# TinyGController_V2.net
KiCad netlist of a schematic drawn in EAGLE
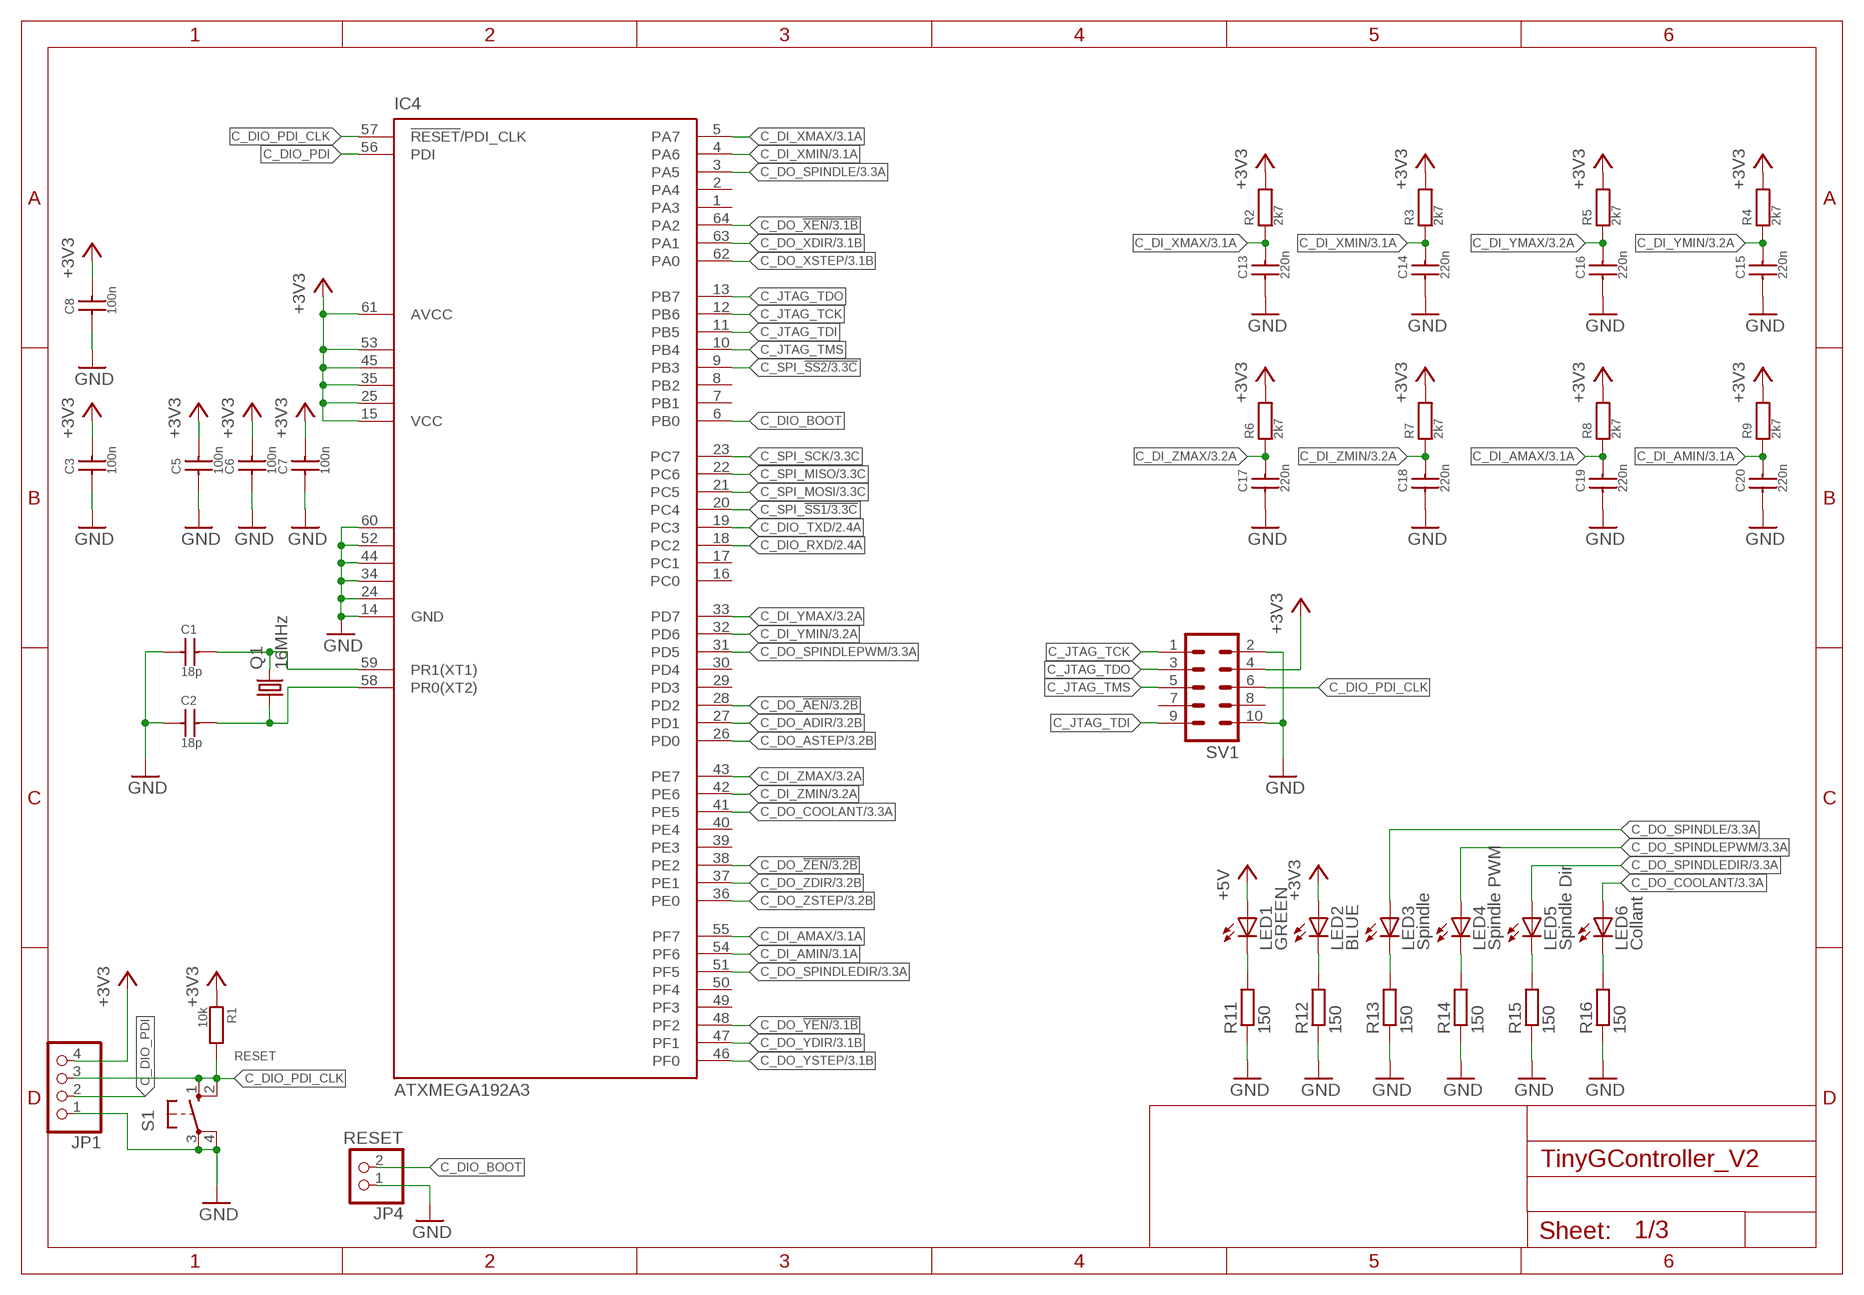
[diagram p0: schematic, sheet 1]
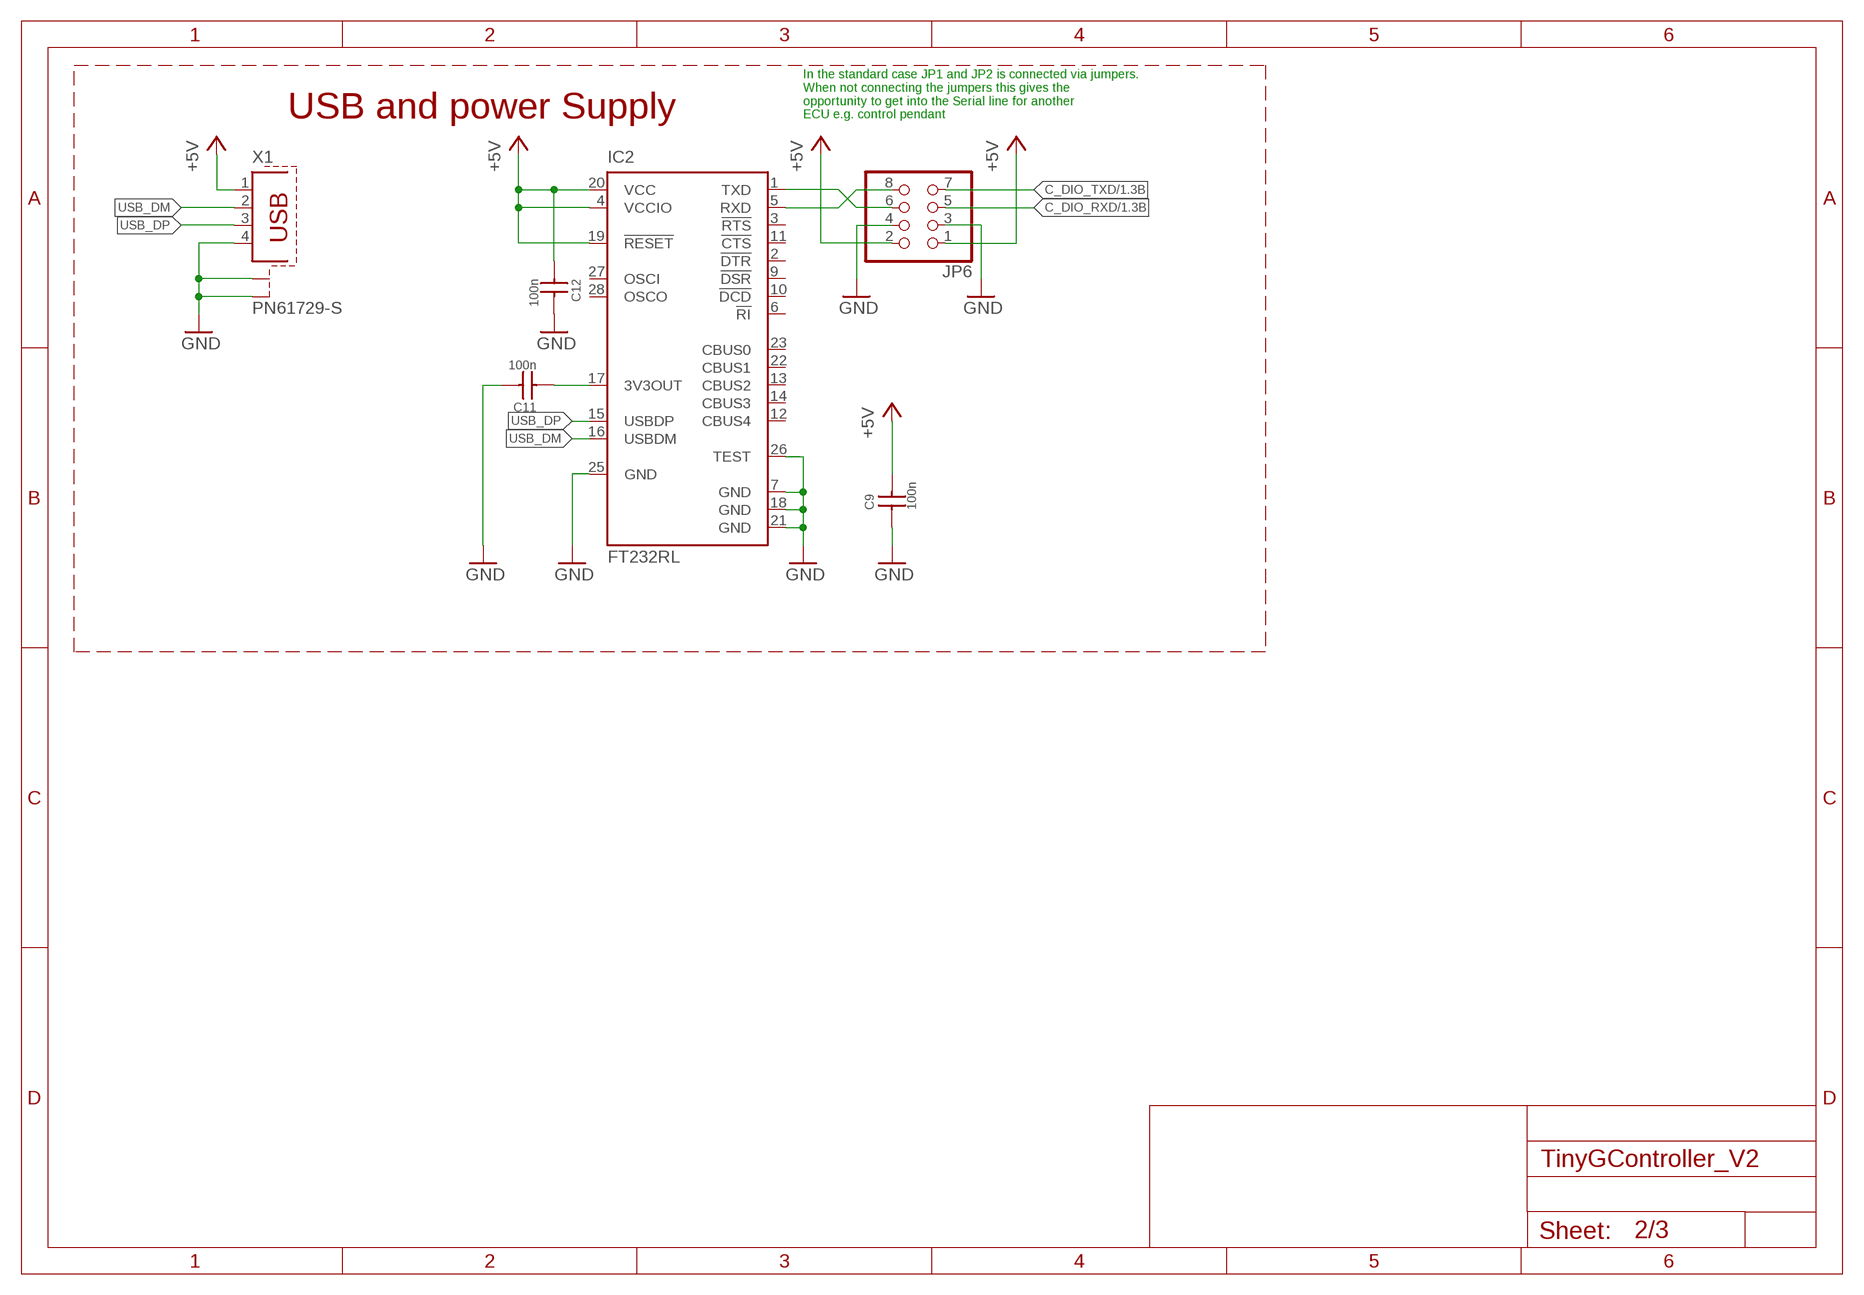
[diagram p1: schematic, sheet 2]
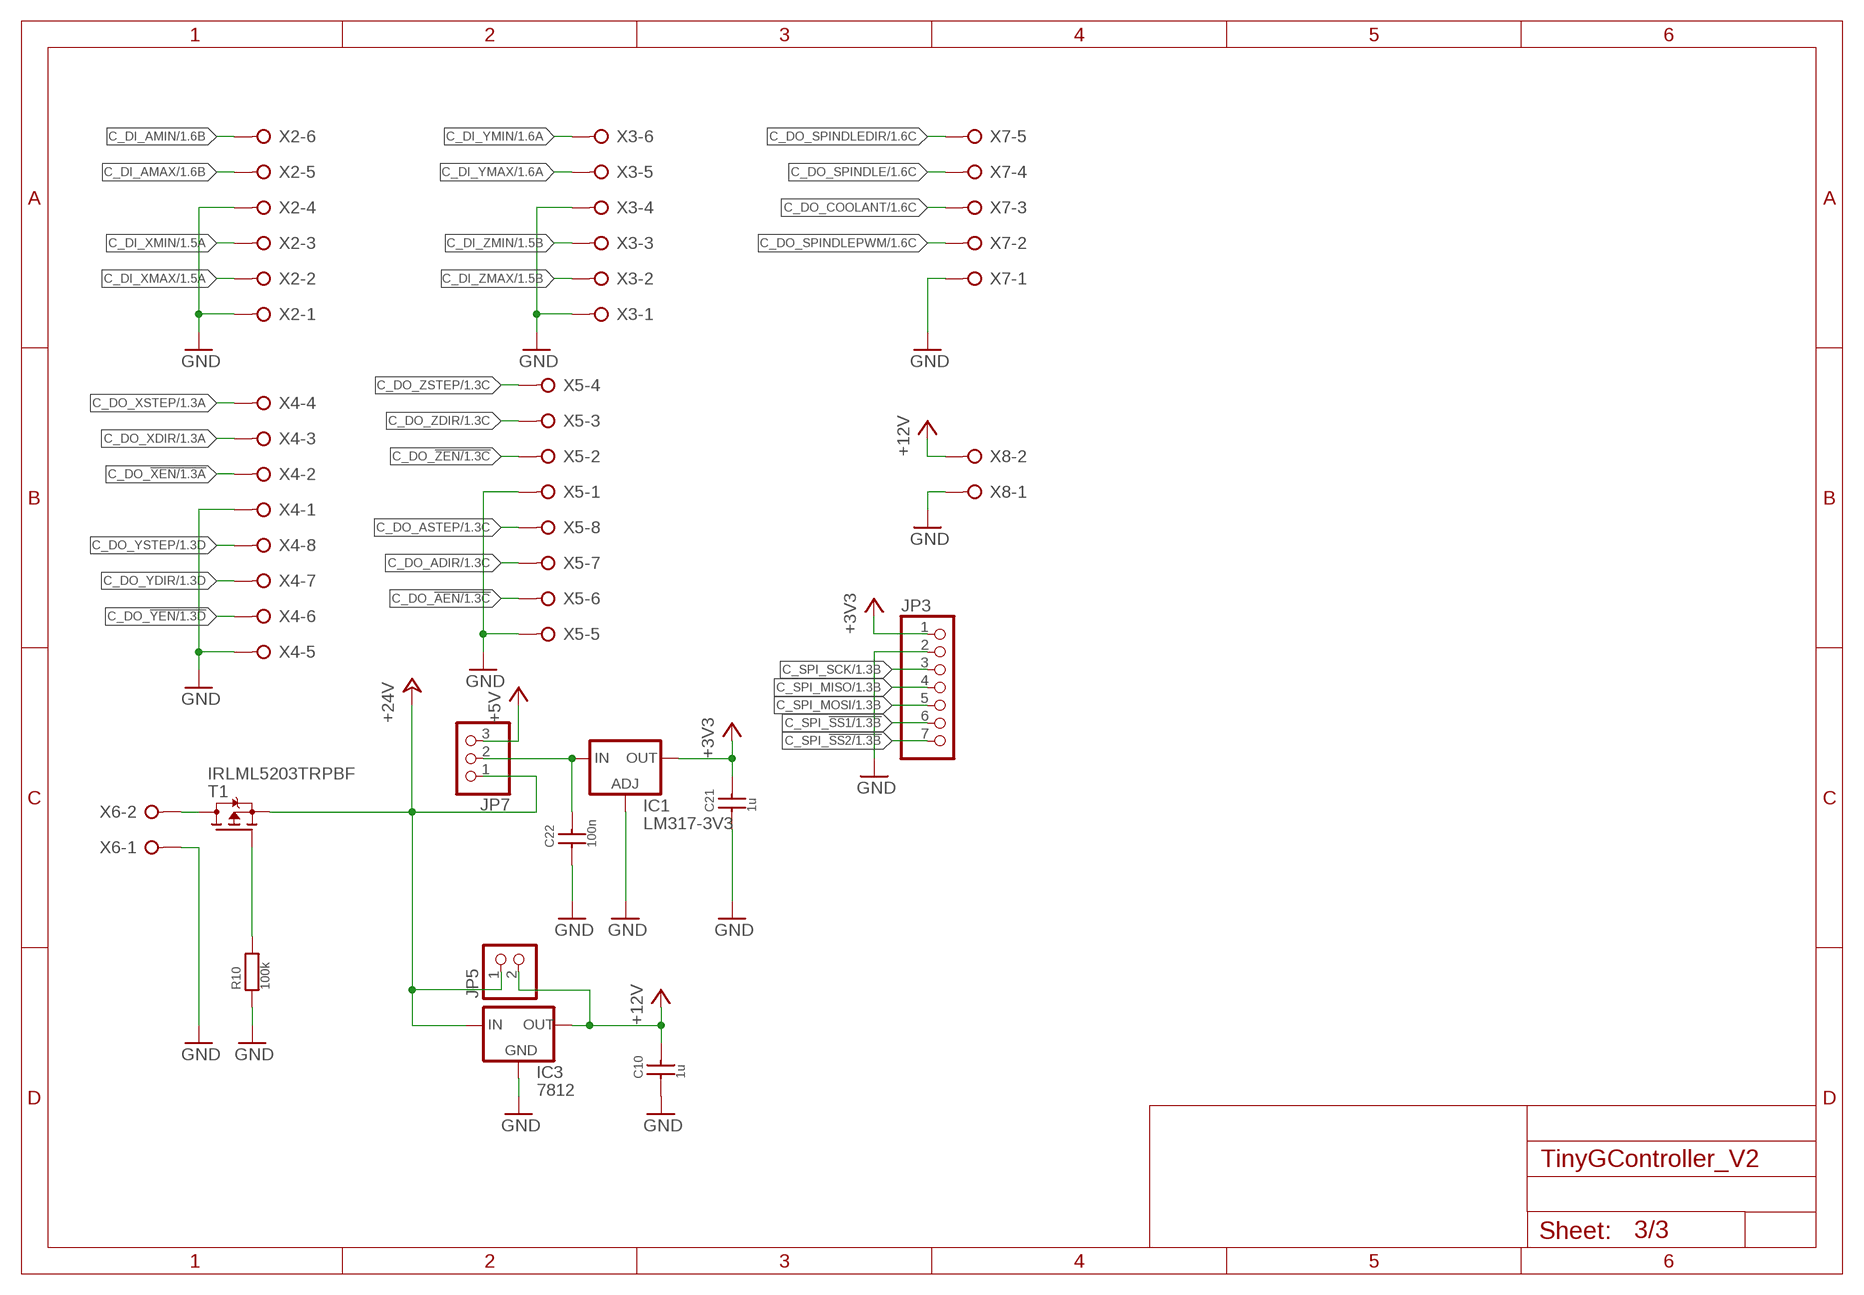
[diagram p2: schematic, sheet 3]

(export (version "E")
  (design (tool "Eeschema 10.0.6"))
  (components
    (comp (ref "C10")
      (value "1u")
      (footprint "eagle-import:C0805")
      (libsource (lib "eagle-import") (part "C_SMD0805"))
    )
    (comp (ref "C21")
      (value "1u")
      (footprint "eagle-import:C0805")
      (libsource (lib "eagle-import") (part "C_SMD0805"))
    )
    (comp (ref "C22")
      (value "100n")
      (footprint "eagle-import:C0805")
      (libsource (lib "eagle-import") (part "C_SMD0805"))
    )
    (comp (ref "IC1")
      (value "LM317-3V3")
      (footprint "eagle-import:SOT223")
      (libsource (lib "eagle-import") (part "LM317?MBSTT3"))
    )
    (comp (ref "IC3")
      (value "7812")
      (footprint "eagle-import:78XXS")
      (libsource (lib "eagle-import") (part "78XXS"))
    )
    (comp (ref "JP3")
      (value "PINHD-1X7")
      (footprint "eagle-import:1X07")
      (libsource (lib "eagle-import") (part "PINHD-1X7"))
    )
    (comp (ref "JP5")
      (value "PINHD-1X2")
      (footprint "eagle-import:1X02")
      (libsource (lib "eagle-import") (part "PINHD-1X2"))
    )
    (comp (ref "JP7")
      (value "PINHD-1X3")
      (footprint "eagle-import:1X03")
      (libsource (lib "eagle-import") (part "PINHD-1X3"))
    )
    (comp (ref "R10")
      (value "100k")
      (footprint "eagle-import:R0603")
      (libsource (lib "eagle-import") (part "R0603"))
    )
    (comp (ref "T1")
      (value "IRLML5203TRPBF")
      (footprint "eagle-import:SOT23")
      (libsource (lib "eagle-import") (part "IRLML5203TRPBF"))
    )
    (comp (ref "X2")
      (value "W237-06P")
      (footprint "eagle-import:W237-6P")
      (libsource (lib "eagle-import") (part "W237-06P"))
    )
    (comp (ref "X3")
      (value "W237-06P")
      (footprint "eagle-import:W237-6P")
      (libsource (lib "eagle-import") (part "W237-06P"))
    )
    (comp (ref "X4")
      (value "W237-08P")
      (footprint "eagle-import:W237-8P")
      (libsource (lib "eagle-import") (part "W237-08P"))
    )
    (comp (ref "X5")
      (value "W237-08P")
      (footprint "eagle-import:W237-8P")
      (libsource (lib "eagle-import") (part "W237-08P"))
    )
    (comp (ref "X6")
      (value "W237-02P")
      (footprint "eagle-import:W237-132")
      (libsource (lib "eagle-import") (part "W237-02P"))
    )
    (comp (ref "X7")
      (value "W237-05P")
      (footprint "eagle-import:W237-5P")
      (libsource (lib "eagle-import") (part "W237-05P"))
    )
    (comp (ref "X8")
      (value "W237-02P")
      (footprint "eagle-import:W237-132")
      (libsource (lib "eagle-import") (part "W237-02P"))
    )
    (comp (ref "C9")
      (value "100n")
      (footprint "eagle-import:C0603")
      (libsource (lib "eagle-import") (part "C_SMD0603"))
    )
    (comp (ref "C11")
      (value "100n")
      (footprint "eagle-import:C0603")
      (libsource (lib "eagle-import") (part "C_SMD0603"))
    )
    (comp (ref "C12")
      (value "100n")
      (footprint "eagle-import:C0603")
      (libsource (lib "eagle-import") (part "C_SMD0603"))
    )
    (comp (ref "IC2")
      (value "FT232RL")
      (footprint "eagle-import:SSOP28")
      (libsource (lib "eagle-import") (part "FT232RL"))
    )
    (comp (ref "JP6")
      (value "PINHD-2X4")
      (footprint "eagle-import:2X04")
      (libsource (lib "eagle-import") (part "PINHD-2X4"))
    )
    (comp (ref "X1")
      (value "PN61729-S")
      (footprint "eagle-import:PN61729-S")
      (libsource (lib "eagle-import") (part "PN61729-S"))
    )
    (comp (ref "C1")
      (value "18p")
      (footprint "eagle-import:C0603")
      (libsource (lib "eagle-import") (part "C_SMD0603"))
    )
    (comp (ref "C2")
      (value "18p")
      (footprint "eagle-import:C0603")
      (libsource (lib "eagle-import") (part "C_SMD0603"))
    )
    (comp (ref "C3")
      (value "100n")
      (footprint "eagle-import:C0603")
      (libsource (lib "eagle-import") (part "C_SMD0603"))
    )
    (comp (ref "C5")
      (value "100n")
      (footprint "eagle-import:C0603")
      (libsource (lib "eagle-import") (part "C_SMD0603"))
    )
    (comp (ref "C6")
      (value "100n")
      (footprint "eagle-import:C0603")
      (libsource (lib "eagle-import") (part "C_SMD0603"))
    )
    (comp (ref "C7")
      (value "100n")
      (footprint "eagle-import:C0603")
      (libsource (lib "eagle-import") (part "C_SMD0603"))
    )
    (comp (ref "C8")
      (value "100n")
      (footprint "eagle-import:C0603")
      (libsource (lib "eagle-import") (part "C_SMD0603"))
    )
    (comp (ref "C13")
      (value "220n")
      (footprint "eagle-import:C0805")
      (libsource (lib "eagle-import") (part "C_SMD0805"))
    )
    (comp (ref "C14")
      (value "220n")
      (footprint "eagle-import:C0805")
      (libsource (lib "eagle-import") (part "C_SMD0805"))
    )
    (comp (ref "C15")
      (value "220n")
      (footprint "eagle-import:C0805")
      (libsource (lib "eagle-import") (part "C_SMD0805"))
    )
    (comp (ref "C16")
      (value "220n")
      (footprint "eagle-import:C0805")
      (libsource (lib "eagle-import") (part "C_SMD0805"))
    )
    (comp (ref "C17")
      (value "220n")
      (footprint "eagle-import:C0805")
      (libsource (lib "eagle-import") (part "C_SMD0805"))
    )
    (comp (ref "C18")
      (value "220n")
      (footprint "eagle-import:C0805")
      (libsource (lib "eagle-import") (part "C_SMD0805"))
    )
    (comp (ref "C19")
      (value "220n")
      (footprint "eagle-import:C0805")
      (libsource (lib "eagle-import") (part "C_SMD0805"))
    )
    (comp (ref "C20")
      (value "220n")
      (footprint "eagle-import:C0805")
      (libsource (lib "eagle-import") (part "C_SMD0805"))
    )
    (comp (ref "IC4")
      (value "ATXMEGA192A3")
      (footprint "eagle-import:TQFP64-0.8MM")
      (libsource (lib "eagle-import") (part "ATXMEGA192A3"))
    )
    (comp (ref "JP1")
      (value "PINHD-1X4")
      (footprint "eagle-import:1X04")
      (libsource (lib "eagle-import") (part "PINHD-1X4"))
    )
    (comp (ref "JP4")
      (value "RESET")
      (footprint "eagle-import:1X02")
      (libsource (lib "eagle-import") (part "PINHD-1X2"))
    )
    (comp (ref "LED1")
      (value "GREEN")
      (footprint "eagle-import:CHIPLED_0805")
      (libsource (lib "eagle-import") (part "LEDCHIPLED_0805"))
    )
    (comp (ref "LED2")
      (value "BLUE")
      (footprint "eagle-import:CHIPLED_0805")
      (libsource (lib "eagle-import") (part "LEDCHIPLED_0805"))
    )
    (comp (ref "LED3")
      (value "Spindle")
      (footprint "eagle-import:CHIPLED_0805")
      (libsource (lib "eagle-import") (part "LEDCHIPLED_0805"))
    )
    (comp (ref "LED4")
      (value "Spindle PWM")
      (footprint "eagle-import:CHIPLED_0805")
      (libsource (lib "eagle-import") (part "LEDCHIPLED_0805"))
    )
    (comp (ref "LED5")
      (value "Spindle Dir")
      (footprint "eagle-import:CHIPLED_0805")
      (libsource (lib "eagle-import") (part "LEDCHIPLED_0805"))
    )
    (comp (ref "LED6")
      (value "Collant")
      (footprint "eagle-import:CHIPLED_0805")
      (libsource (lib "eagle-import") (part "LEDCHIPLED_0805"))
    )
    (comp (ref "Q1")
      (value "16MHz")
      (footprint "eagle-import:HC49_USSM")
      (libsource (lib "eagle-import") (part "ATS073ASM-1"))
    )
    (comp (ref "R1")
      (value "10k")
      (footprint "eagle-import:R0603")
      (libsource (lib "eagle-import") (part "R0603"))
    )
    (comp (ref "R2")
      (value "2k7")
      (footprint "eagle-import:R0603")
      (libsource (lib "eagle-import") (part "R0603"))
    )
    (comp (ref "R3")
      (value "2k7")
      (footprint "eagle-import:R0603")
      (libsource (lib "eagle-import") (part "R0603"))
    )
    (comp (ref "R4")
      (value "2k7")
      (footprint "eagle-import:R0603")
      (libsource (lib "eagle-import") (part "R0603"))
    )
    (comp (ref "R5")
      (value "2k7")
      (footprint "eagle-import:R0603")
      (libsource (lib "eagle-import") (part "R0603"))
    )
    (comp (ref "R6")
      (value "2k7")
      (footprint "eagle-import:R0603")
      (libsource (lib "eagle-import") (part "R0603"))
    )
    (comp (ref "R7")
      (value "2k7")
      (footprint "eagle-import:R0603")
      (libsource (lib "eagle-import") (part "R0603"))
    )
    (comp (ref "R8")
      (value "2k7")
      (footprint "eagle-import:R0603")
      (libsource (lib "eagle-import") (part "R0603"))
    )
    (comp (ref "R9")
      (value "2k7")
      (footprint "eagle-import:R0603")
      (libsource (lib "eagle-import") (part "R0603"))
    )
    (comp (ref "R11")
      (value "150")
      (footprint "eagle-import:R0603")
      (libsource (lib "eagle-import") (part "R-EU_R0603"))
    )
    (comp (ref "R12")
      (value "150")
      (footprint "eagle-import:R0603")
      (libsource (lib "eagle-import") (part "R-EU_R0603"))
    )
    (comp (ref "R13")
      (value "150")
      (footprint "eagle-import:R0603")
      (libsource (lib "eagle-import") (part "R-EU_R0603"))
    )
    (comp (ref "R14")
      (value "150")
      (footprint "eagle-import:R0603")
      (libsource (lib "eagle-import") (part "R-EU_R0603"))
    )
    (comp (ref "R15")
      (value "150")
      (footprint "eagle-import:R0603")
      (libsource (lib "eagle-import") (part "R-EU_R0603"))
    )
    (comp (ref "R16")
      (value "150")
      (footprint "eagle-import:R0603")
      (libsource (lib "eagle-import") (part "R-EU_R0603"))
    )
    (comp (ref "S1")
      (value "10-XX")
      (footprint "eagle-import:B3F-10XX")
      (fields (field (name "MPN") "B3F-1000"))
      (libsource (lib "eagle-import") (part "10-XX"))
    )
    (comp (ref "SV1")
      (value "ML10")
      (footprint "eagle-import:ML10")
      (libsource (lib "eagle-import") (part "ML10"))
    )
  )
  (nets
    (net (code "1") (name "+3V3") (class "Default")
      (node (ref "C21") (pin "2") (pinfunction "P$2_2") (pintype "passive"))
      (node (ref "C3") (pin "2") (pinfunction "P$2_2") (pintype "passive"))
      (node (ref "C5") (pin "2") (pinfunction "P$2_2") (pintype "passive"))
      (node (ref "C6") (pin "2") (pinfunction "P$2_2") (pintype "passive"))
      (node (ref "C7") (pin "2") (pinfunction "P$2_2") (pintype "passive"))
      (node (ref "C8") (pin "2") (pinfunction "P$2_2") (pintype "passive"))
      (node (ref "IC1") (pin "4") (pinfunction "OUT_4") (pintype "passive"))
      (node (ref "IC4") (pin "15") (pinfunction "VCC_15") (pintype "power_in"))
      (node (ref "IC4") (pin "25") (pinfunction "VCC1_25") (pintype "power_in"))
      (node (ref "IC4") (pin "35") (pinfunction "VCC2_35") (pintype "power_in"))
      (node (ref "IC4") (pin "45") (pinfunction "VCC3_45") (pintype "power_in"))
      (node (ref "IC4") (pin "53") (pinfunction "VCC4_53") (pintype "power_in"))
      (node (ref "IC4") (pin "61") (pinfunction "AVCC_61") (pintype "power_in"))
      (node (ref "JP1") (pin "4") (pinfunction "4_4") (pintype "passive"))
      (node (ref "JP3") (pin "1") (pinfunction "1_1") (pintype "passive"))
      (node (ref "LED2") (pin "A") (pinfunction "A_A") (pintype "passive"))
      (node (ref "R1") (pin "1") (pinfunction "P$1_1") (pintype "passive"))
      (node (ref "R2") (pin "2") (pinfunction "P$2_2") (pintype "passive"))
      (node (ref "R3") (pin "2") (pinfunction "P$2_2") (pintype "passive"))
      (node (ref "R4") (pin "2") (pinfunction "P$2_2") (pintype "passive"))
      (node (ref "R5") (pin "2") (pinfunction "P$2_2") (pintype "passive"))
      (node (ref "R6") (pin "2") (pinfunction "P$2_2") (pintype "passive"))
      (node (ref "R7") (pin "2") (pinfunction "P$2_2") (pintype "passive"))
      (node (ref "R8") (pin "2") (pinfunction "P$2_2") (pintype "passive"))
      (node (ref "R9") (pin "2") (pinfunction "P$2_2") (pintype "passive"))
      (node (ref "SV1") (pin "4") (pinfunction "4_4") (pintype "passive"))
    )
    (net (code "2") (name "+5V") (class "Default")
      (node (ref "C12") (pin "1") (pinfunction "P$1_1") (pintype "passive"))
      (node (ref "C9") (pin "2") (pinfunction "P$2_2") (pintype "passive"))
      (node (ref "IC2") (pin "19") (pinfunction "~{RESET}_19") (pintype "input"))
      (node (ref "IC2") (pin "20") (pinfunction "VCC_20") (pintype "power_in"))
      (node (ref "IC2") (pin "4") (pinfunction "VCCIO_4") (pintype "power_in"))
      (node (ref "JP6") (pin "1") (pinfunction "1_1") (pintype "passive"))
      (node (ref "JP6") (pin "2") (pinfunction "2_2") (pintype "passive"))
      (node (ref "JP7") (pin "3") (pinfunction "3_3") (pintype "passive"))
      (node (ref "LED1") (pin "A") (pinfunction "A_A") (pintype "passive"))
      (node (ref "X1") (pin "1") (pinfunction "1_1") (pintype "passive"))
    )
    (net (code "3") (name "+12V") (class "Default")
      (node (ref "C10") (pin "2") (pinfunction "P$2_2") (pintype "passive"))
      (node (ref "IC3") (pin "OUT") (pinfunction "OUT_OUT") (pintype "passive"))
      (node (ref "JP5") (pin "2") (pinfunction "2_2") (pintype "passive"))
      (node (ref "X8") (pin "2") (pinfunction "KL_2") (pintype "passive"))
    )
    (net (code "4") (name "+24V") (class "Default")
      (node (ref "IC3") (pin "IN") (pinfunction "IN_IN") (pintype "input"))
      (node (ref "JP5") (pin "1") (pinfunction "1_1") (pintype "passive"))
      (node (ref "JP7") (pin "1") (pinfunction "1_1") (pintype "passive"))
      (node (ref "T1") (pin "2") (pinfunction "S_2") (pintype "passive"))
    )
    (net (code "5") (name "C_DIO_BOOT") (class "Default")
      (node (ref "IC4") (pin "6") (pinfunction "PB0_6") (pintype "bidirectional"))
      (node (ref "JP4") (pin "2") (pinfunction "2_2") (pintype "passive"))
    )
    (net (code "6") (name "C_DIO_PDI") (class "Default")
      (node (ref "IC4") (pin "56") (pinfunction "PDI_56") (pintype "input"))
      (node (ref "JP1") (pin "2") (pinfunction "2_2") (pintype "passive"))
    )
    (net (code "7") (name "C_DIO_PDI_CLK") (class "Default")
      (node (ref "IC4") (pin "57") (pinfunction "~{RESET}/PDI_CLK_57") (pintype "input"))
      (node (ref "JP1") (pin "3") (pinfunction "3_3") (pintype "passive"))
      (node (ref "R1") (pin "2") (pinfunction "P$2_2") (pintype "passive"))
      (node (ref "S1") (pin "1") (pinfunction "S_1") (pintype "passive"))
      (node (ref "S1") (pin "2") (pinfunction "S1_2") (pintype "passive"))
      (node (ref "SV1") (pin "6") (pinfunction "6_6") (pintype "passive"))
    )
    (net (code "8") (name "C_DIO_RXD") (class "Default")
      (node (ref "IC4") (pin "18") (pinfunction "PC2_18") (pintype "bidirectional"))
      (node (ref "JP6") (pin "5") (pinfunction "5_5") (pintype "passive"))
    )
    (net (code "9") (name "C_DIO_TXD") (class "Default")
      (node (ref "IC4") (pin "19") (pinfunction "PC3_19") (pintype "bidirectional"))
      (node (ref "JP6") (pin "7") (pinfunction "7_7") (pintype "passive"))
    )
    (net (code "10") (name "C_DI_AMAX") (class "Default")
      (node (ref "C19") (pin "2") (pinfunction "P$2_2") (pintype "passive"))
      (node (ref "IC4") (pin "55") (pinfunction "PF7_55") (pintype "bidirectional"))
      (node (ref "R8") (pin "1") (pinfunction "P$1_1") (pintype "passive"))
      (node (ref "X2") (pin "5") (pinfunction "KL_5") (pintype "passive"))
    )
    (net (code "11") (name "C_DI_AMIN") (class "Default")
      (node (ref "C20") (pin "2") (pinfunction "P$2_2") (pintype "passive"))
      (node (ref "IC4") (pin "54") (pinfunction "PF6_54") (pintype "bidirectional"))
      (node (ref "R9") (pin "1") (pinfunction "P$1_1") (pintype "passive"))
      (node (ref "X2") (pin "6") (pinfunction "KL_6") (pintype "passive"))
    )
    (net (code "12") (name "C_DI_XMAX") (class "Default")
      (node (ref "C13") (pin "2") (pinfunction "P$2_2") (pintype "passive"))
      (node (ref "IC4") (pin "5") (pinfunction "PA7_5") (pintype "bidirectional"))
      (node (ref "R2") (pin "1") (pinfunction "P$1_1") (pintype "passive"))
      (node (ref "X2") (pin "2") (pinfunction "KL_2") (pintype "passive"))
    )
    (net (code "13") (name "C_DI_XMIN") (class "Default")
      (node (ref "C14") (pin "2") (pinfunction "P$2_2") (pintype "passive"))
      (node (ref "IC4") (pin "4") (pinfunction "PA6_4") (pintype "bidirectional"))
      (node (ref "R3") (pin "1") (pinfunction "P$1_1") (pintype "passive"))
      (node (ref "X2") (pin "3") (pinfunction "KL_3") (pintype "passive"))
    )
    (net (code "14") (name "C_DI_YMAX") (class "Default")
      (node (ref "C16") (pin "2") (pinfunction "P$2_2") (pintype "passive"))
      (node (ref "IC4") (pin "33") (pinfunction "PD7_33") (pintype "bidirectional"))
      (node (ref "R5") (pin "1") (pinfunction "P$1_1") (pintype "passive"))
      (node (ref "X3") (pin "5") (pinfunction "KL_5") (pintype "passive"))
    )
    (net (code "15") (name "C_DI_YMIN") (class "Default")
      (node (ref "C15") (pin "2") (pinfunction "P$2_2") (pintype "passive"))
      (node (ref "IC4") (pin "32") (pinfunction "PD6_32") (pintype "bidirectional"))
      (node (ref "R4") (pin "1") (pinfunction "P$1_1") (pintype "passive"))
      (node (ref "X3") (pin "6") (pinfunction "KL_6") (pintype "passive"))
    )
    (net (code "16") (name "C_DI_ZMAX") (class "Default")
      (node (ref "C17") (pin "2") (pinfunction "P$2_2") (pintype "passive"))
      (node (ref "IC4") (pin "43") (pinfunction "PE7_43") (pintype "bidirectional"))
      (node (ref "R6") (pin "1") (pinfunction "P$1_1") (pintype "passive"))
      (node (ref "X3") (pin "2") (pinfunction "KL_2") (pintype "passive"))
    )
    (net (code "17") (name "C_DI_ZMIN") (class "Default")
      (node (ref "C18") (pin "2") (pinfunction "P$2_2") (pintype "passive"))
      (node (ref "IC4") (pin "42") (pinfunction "PE6_42") (pintype "bidirectional"))
      (node (ref "R7") (pin "1") (pinfunction "P$1_1") (pintype "passive"))
      (node (ref "X3") (pin "3") (pinfunction "KL_3") (pintype "passive"))
    )
    (net (code "18") (name "C_DO_ADIR") (class "Default")
      (node (ref "IC4") (pin "27") (pinfunction "PD1_27") (pintype "bidirectional"))
      (node (ref "X5") (pin "7") (pinfunction "KL_7") (pintype "passive"))
    )
    (net (code "19") (name "C_DO_ASTEP") (class "Default")
      (node (ref "IC4") (pin "26") (pinfunction "PD0_26") (pintype "bidirectional"))
      (node (ref "X5") (pin "8") (pinfunction "KL_8") (pintype "passive"))
    )
    (net (code "20") (name "C_DO_COOLANT") (class "Default")
      (node (ref "IC4") (pin "41") (pinfunction "PE5_41") (pintype "bidirectional"))
      (node (ref "LED6") (pin "A") (pinfunction "A_A") (pintype "passive"))
      (node (ref "X7") (pin "3") (pinfunction "KL_3") (pintype "passive"))
    )
    (net (code "21") (name "C_DO_SPINDLE") (class "Default")
      (node (ref "IC4") (pin "3") (pinfunction "PA5_3") (pintype "bidirectional"))
      (node (ref "LED3") (pin "A") (pinfunction "A_A") (pintype "passive"))
      (node (ref "X7") (pin "4") (pinfunction "KL_4") (pintype "passive"))
    )
    (net (code "22") (name "C_DO_SPINDLEDIR") (class "Default")
      (node (ref "IC4") (pin "51") (pinfunction "PF5_51") (pintype "bidirectional"))
      (node (ref "LED5") (pin "A") (pinfunction "A_A") (pintype "passive"))
      (node (ref "X7") (pin "5") (pinfunction "KL_5") (pintype "passive"))
    )
    (net (code "23") (name "C_DO_SPINDLEPWM") (class "Default")
      (node (ref "IC4") (pin "31") (pinfunction "PD5_31") (pintype "bidirectional"))
      (node (ref "LED4") (pin "A") (pinfunction "A_A") (pintype "passive"))
      (node (ref "X7") (pin "2") (pinfunction "KL_2") (pintype "passive"))
    )
    (net (code "24") (name "C_DO_XDIR") (class "Default")
      (node (ref "IC4") (pin "63") (pinfunction "PA1_63") (pintype "bidirectional"))
      (node (ref "X4") (pin "3") (pinfunction "KL_3") (pintype "passive"))
    )
    (net (code "25") (name "C_DO_XSTEP") (class "Default")
      (node (ref "IC4") (pin "62") (pinfunction "PA0_62") (pintype "bidirectional"))
      (node (ref "X4") (pin "4") (pinfunction "KL_4") (pintype "passive"))
    )
    (net (code "26") (name "C_DO_YDIR") (class "Default")
      (node (ref "IC4") (pin "47") (pinfunction "PF1_47") (pintype "bidirectional"))
      (node (ref "X4") (pin "7") (pinfunction "KL_7") (pintype "passive"))
    )
    (net (code "27") (name "C_DO_YSTEP") (class "Default")
      (node (ref "IC4") (pin "46") (pinfunction "PF0_46") (pintype "bidirectional"))
      (node (ref "X4") (pin "8") (pinfunction "KL_8") (pintype "passive"))
    )
    (net (code "28") (name "C_DO_ZDIR") (class "Default")
      (node (ref "IC4") (pin "37") (pinfunction "PE1_37") (pintype "bidirectional"))
      (node (ref "X5") (pin "3") (pinfunction "KL_3") (pintype "passive"))
    )
    (net (code "29") (name "C_DO_ZSTEP") (class "Default")
      (node (ref "IC4") (pin "36") (pinfunction "PE0_36") (pintype "bidirectional"))
      (node (ref "X5") (pin "4") (pinfunction "KL_4") (pintype "passive"))
    )
    (net (code "30") (name "C_DO_~{AEN}") (class "Default")
      (node (ref "IC4") (pin "28") (pinfunction "PD2_28") (pintype "bidirectional"))
      (node (ref "X5") (pin "6") (pinfunction "KL_6") (pintype "passive"))
    )
    (net (code "31") (name "C_DO_~{XEN}") (class "Default")
      (node (ref "IC4") (pin "64") (pinfunction "PA2_64") (pintype "bidirectional"))
      (node (ref "X4") (pin "2") (pinfunction "KL_2") (pintype "passive"))
    )
    (net (code "32") (name "C_DO_~{YEN}") (class "Default")
      (node (ref "IC4") (pin "48") (pinfunction "PF2_48") (pintype "bidirectional"))
      (node (ref "X4") (pin "6") (pinfunction "KL_6") (pintype "passive"))
    )
    (net (code "33") (name "C_DO_~{ZEN}") (class "Default")
      (node (ref "IC4") (pin "38") (pinfunction "PE2_38") (pintype "bidirectional"))
      (node (ref "X5") (pin "2") (pinfunction "KL_2") (pintype "passive"))
    )
    (net (code "34") (name "C_JTAG_TCK") (class "Default")
      (node (ref "IC4") (pin "12") (pinfunction "PB6_12") (pintype "bidirectional"))
      (node (ref "SV1") (pin "1") (pinfunction "1_1") (pintype "passive"))
    )
    (net (code "35") (name "C_JTAG_TDI") (class "Default")
      (node (ref "IC4") (pin "11") (pinfunction "PB5_11") (pintype "bidirectional"))
      (node (ref "SV1") (pin "9") (pinfunction "9_9") (pintype "passive"))
    )
    (net (code "36") (name "C_JTAG_TDO") (class "Default")
      (node (ref "IC4") (pin "13") (pinfunction "PB7_13") (pintype "bidirectional"))
      (node (ref "SV1") (pin "3") (pinfunction "3_3") (pintype "passive"))
    )
    (net (code "37") (name "C_JTAG_TMS") (class "Default")
      (node (ref "IC4") (pin "10") (pinfunction "PB4_10") (pintype "bidirectional"))
      (node (ref "SV1") (pin "5") (pinfunction "5_5") (pintype "passive"))
    )
    (net (code "38") (name "C_SPI_MISO") (class "Default")
      (node (ref "IC4") (pin "22") (pinfunction "PC6_22") (pintype "bidirectional"))
      (node (ref "JP3") (pin "4") (pinfunction "4_4") (pintype "passive"))
    )
    (net (code "39") (name "C_SPI_MOSI") (class "Default")
      (node (ref "IC4") (pin "21") (pinfunction "PC5_21") (pintype "bidirectional"))
      (node (ref "JP3") (pin "5") (pinfunction "5_5") (pintype "passive"))
    )
    (net (code "40") (name "C_SPI_SCK") (class "Default")
      (node (ref "IC4") (pin "23") (pinfunction "PC7_23") (pintype "bidirectional"))
      (node (ref "JP3") (pin "3") (pinfunction "3_3") (pintype "passive"))
    )
    (net (code "41") (name "C_SPI_~{SS1}") (class "Default")
      (node (ref "IC4") (pin "20") (pinfunction "PC4_20") (pintype "bidirectional"))
      (node (ref "JP3") (pin "6") (pinfunction "6_6") (pintype "passive"))
    )
    (net (code "42") (name "C_SPI_~{SS2}") (class "Default")
      (node (ref "IC4") (pin "9") (pinfunction "PB3_9") (pintype "bidirectional"))
      (node (ref "JP3") (pin "7") (pinfunction "7_7") (pintype "passive"))
    )
    (net (code "43") (name "GND") (class "Default")
      (node (ref "C1") (pin "1") (pinfunction "P$1_1") (pintype "passive"))
      (node (ref "C10") (pin "1") (pinfunction "P$1_1") (pintype "passive"))
      (node (ref "C11") (pin "2") (pinfunction "P$2_2") (pintype "passive"))
      (node (ref "C12") (pin "2") (pinfunction "P$2_2") (pintype "passive"))
      (node (ref "C13") (pin "1") (pinfunction "P$1_1") (pintype "passive"))
      (node (ref "C14") (pin "1") (pinfunction "P$1_1") (pintype "passive"))
      (node (ref "C15") (pin "1") (pinfunction "P$1_1") (pintype "passive"))
      (node (ref "C16") (pin "1") (pinfunction "P$1_1") (pintype "passive"))
      (node (ref "C17") (pin "1") (pinfunction "P$1_1") (pintype "passive"))
      (node (ref "C18") (pin "1") (pinfunction "P$1_1") (pintype "passive"))
      (node (ref "C19") (pin "1") (pinfunction "P$1_1") (pintype "passive"))
      (node (ref "C2") (pin "1") (pinfunction "P$1_1") (pintype "passive"))
      (node (ref "C20") (pin "1") (pinfunction "P$1_1") (pintype "passive"))
      (node (ref "C21") (pin "1") (pinfunction "P$1_1") (pintype "passive"))
      (node (ref "C22") (pin "1") (pinfunction "P$1_1") (pintype "passive"))
      (node (ref "C3") (pin "1") (pinfunction "P$1_1") (pintype "passive"))
      (node (ref "C5") (pin "1") (pinfunction "P$1_1") (pintype "passive"))
      (node (ref "C6") (pin "1") (pinfunction "P$1_1") (pintype "passive"))
      (node (ref "C7") (pin "1") (pinfunction "P$1_1") (pintype "passive"))
      (node (ref "C8") (pin "1") (pinfunction "P$1_1") (pintype "passive"))
      (node (ref "C9") (pin "1") (pinfunction "P$1_1") (pintype "passive"))
      (node (ref "IC1") (pin "1") (pinfunction "ADJ_1") (pintype "input"))
      (node (ref "IC2") (pin "18") (pinfunction "GND_18") (pintype "power_in"))
      (node (ref "IC2") (pin "21") (pinfunction "GND_21") (pintype "power_in"))
      (node (ref "IC2") (pin "25") (pinfunction "GND_25") (pintype "power_in"))
      (node (ref "IC2") (pin "26") (pinfunction "TEST_26") (pintype "input"))
      (node (ref "IC2") (pin "7") (pinfunction "GND_7") (pintype "power_in"))
      (node (ref "IC3") (pin "GND") (pinfunction "GND_GND") (pintype "input"))
      (node (ref "IC4") (pin "14") (pinfunction "GND_14") (pintype "power_in"))
      (node (ref "IC4") (pin "24") (pinfunction "GND1_24") (pintype "power_in"))
      (node (ref "IC4") (pin "34") (pinfunction "GND2_34") (pintype "power_in"))
      (node (ref "IC4") (pin "44") (pinfunction "GND3_44") (pintype "power_in"))
      (node (ref "IC4") (pin "52") (pinfunction "GND4_52") (pintype "power_in"))
      (node (ref "IC4") (pin "60") (pinfunction "GND5_60") (pintype "power_in"))
      (node (ref "JP1") (pin "1") (pinfunction "1_1") (pintype "passive"))
      (node (ref "JP3") (pin "2") (pinfunction "2_2") (pintype "passive"))
      (node (ref "JP4") (pin "1") (pinfunction "1_1") (pintype "passive"))
      (node (ref "JP6") (pin "3") (pinfunction "3_3") (pintype "passive"))
      (node (ref "JP6") (pin "4") (pinfunction "4_4") (pintype "passive"))
      (node (ref "R10") (pin "1") (pinfunction "P$1_1") (pintype "passive"))
      (node (ref "R11") (pin "1") (pinfunction "1_1") (pintype "passive"))
      (node (ref "R12") (pin "1") (pinfunction "1_1") (pintype "passive"))
      (node (ref "R13") (pin "1") (pinfunction "1_1") (pintype "passive"))
      (node (ref "R14") (pin "1") (pinfunction "1_1") (pintype "passive"))
      (node (ref "R15") (pin "1") (pinfunction "1_1") (pintype "passive"))
      (node (ref "R16") (pin "1") (pinfunction "1_1") (pintype "passive"))
      (node (ref "S1") (pin "3") (pinfunction "P_3") (pintype "passive"))
      (node (ref "S1") (pin "4") (pinfunction "P1_4") (pintype "passive"))
      (node (ref "SV1") (pin "10") (pinfunction "10_10") (pintype "passive"))
      (node (ref "SV1") (pin "2") (pinfunction "2_2") (pintype "passive"))
      (node (ref "X1") (pin "4") (pinfunction "4_4") (pintype "passive"))
      (node (ref "X1") (pin "S1") (pinfunction "S1_S1") (pintype "passive"))
      (node (ref "X1") (pin "S2") (pinfunction "S2_S2") (pintype "passive"))
      (node (ref "X2") (pin "1") (pinfunction "KL_1") (pintype "passive"))
      (node (ref "X2") (pin "4") (pinfunction "KL_4") (pintype "passive"))
      (node (ref "X3") (pin "1") (pinfunction "KL_1") (pintype "passive"))
      (node (ref "X3") (pin "4") (pinfunction "KL_4") (pintype "passive"))
      (node (ref "X4") (pin "1") (pinfunction "KL_1") (pintype "passive"))
      (node (ref "X4") (pin "5") (pinfunction "KL_5") (pintype "passive"))
      (node (ref "X5") (pin "1") (pinfunction "KL_1") (pintype "passive"))
      (node (ref "X5") (pin "5") (pinfunction "KL_5") (pintype "passive"))
      (node (ref "X6") (pin "1") (pinfunction "KL_1") (pintype "passive"))
      (node (ref "X7") (pin "1") (pinfunction "KL_1") (pintype "passive"))
      (node (ref "X8") (pin "1") (pinfunction "KL_1") (pintype "passive"))
    )
    (net (code "44") (name "Net-(C1-P$2)") (class "Default")
      (node (ref "C1") (pin "2") (pinfunction "P$2_2") (pintype "passive"))
      (node (ref "IC4") (pin "59") (pinfunction "PR1(XT1)_59") (pintype "bidirectional"))
      (node (ref "Q1") (pin "2") (pinfunction "2_2") (pintype "passive"))
    )
    (net (code "45") (name "Net-(C2-P$2)") (class "Default")
      (node (ref "C2") (pin "2") (pinfunction "P$2_2") (pintype "passive"))
      (node (ref "IC4") (pin "58") (pinfunction "PR0(XT2)_58") (pintype "bidirectional"))
      (node (ref "Q1") (pin "1") (pinfunction "1_1") (pintype "passive"))
    )
    (net (code "46") (name "Net-(C11-P$1)") (class "Default")
      (node (ref "C11") (pin "1") (pinfunction "P$1_1") (pintype "passive"))
      (node (ref "IC2") (pin "17") (pinfunction "3V3OUT_17") (pintype "output"))
    )
    (net (code "47") (name "Net-(C22-P$2)") (class "Default")
      (node (ref "C22") (pin "2") (pinfunction "P$2_2") (pintype "passive"))
      (node (ref "IC1") (pin "3") (pinfunction "IN_3") (pintype "input"))
      (node (ref "JP7") (pin "2") (pinfunction "2_2") (pintype "passive"))
    )
    (net (code "48") (name "Net-(IC2-RXD)") (class "Default")
      (node (ref "IC2") (pin "5") (pinfunction "RXD_5") (pintype "input"))
      (node (ref "JP6") (pin "8") (pinfunction "8_8") (pintype "passive"))
    )
    (net (code "49") (name "Net-(IC2-TXD)") (class "Default")
      (node (ref "IC2") (pin "1") (pinfunction "TXD_1") (pintype "output"))
      (node (ref "JP6") (pin "6") (pinfunction "6_6") (pintype "passive"))
    )
    (net (code "50") (name "Net-(LED1-PadC)") (class "Default")
      (node (ref "LED1") (pin "C") (pinfunction "C_C") (pintype "passive"))
      (node (ref "R11") (pin "2") (pinfunction "2_2") (pintype "passive"))
    )
    (net (code "51") (name "Net-(LED2-PadC)") (class "Default")
      (node (ref "LED2") (pin "C") (pinfunction "C_C") (pintype "passive"))
      (node (ref "R12") (pin "2") (pinfunction "2_2") (pintype "passive"))
    )
    (net (code "52") (name "Net-(LED3-PadC)") (class "Default")
      (node (ref "LED3") (pin "C") (pinfunction "C_C") (pintype "passive"))
      (node (ref "R13") (pin "2") (pinfunction "2_2") (pintype "passive"))
    )
    (net (code "53") (name "Net-(LED4-PadC)") (class "Default")
      (node (ref "LED4") (pin "C") (pinfunction "C_C") (pintype "passive"))
      (node (ref "R14") (pin "2") (pinfunction "2_2") (pintype "passive"))
    )
    (net (code "54") (name "Net-(LED5-PadC)") (class "Default")
      (node (ref "LED5") (pin "C") (pinfunction "C_C") (pintype "passive"))
      (node (ref "R15") (pin "2") (pinfunction "2_2") (pintype "passive"))
    )
    (net (code "55") (name "Net-(LED6-PadC)") (class "Default")
      (node (ref "LED6") (pin "C") (pinfunction "C_C") (pintype "passive"))
      (node (ref "R16") (pin "2") (pinfunction "2_2") (pintype "passive"))
    )
    (net (code "56") (name "Net-(R10-P$2)") (class "Default")
      (node (ref "R10") (pin "2") (pinfunction "P$2_2") (pintype "passive"))
      (node (ref "T1") (pin "1") (pinfunction "G_1") (pintype "passive"))
    )
    (net (code "57") (name "Net-(T1-D)") (class "Default")
      (node (ref "T1") (pin "3") (pinfunction "D_3") (pintype "passive"))
      (node (ref "X6") (pin "2") (pinfunction "KL_2") (pintype "passive"))
    )
    (net (code "58") (name "USB_DM") (class "Default")
      (node (ref "IC2") (pin "16") (pinfunction "USBDM_16") (pintype "bidirectional"))
      (node (ref "X1") (pin "2") (pinfunction "2_2") (pintype "passive"))
    )
    (net (code "59") (name "USB_DP") (class "Default")
      (node (ref "IC2") (pin "15") (pinfunction "USBDP_15") (pintype "bidirectional"))
      (node (ref "X1") (pin "3") (pinfunction "3_3") (pintype "passive"))
    )
    (net (code "60") (name "unconnected-(IC2-CBUS0-Pad23)") (class "Default")
      (node (ref "IC2") (pin "23") (pinfunction "CBUS0_23") (pintype "bidirectional"))
    )
    (net (code "61") (name "unconnected-(IC2-CBUS1-Pad22)") (class "Default")
      (node (ref "IC2") (pin "22") (pinfunction "CBUS1_22") (pintype "bidirectional"))
    )
    (net (code "62") (name "unconnected-(IC2-CBUS2-Pad13)") (class "Default")
      (node (ref "IC2") (pin "13") (pinfunction "CBUS2_13") (pintype "bidirectional"))
    )
    (net (code "63") (name "unconnected-(IC2-CBUS3-Pad14)") (class "Default")
      (node (ref "IC2") (pin "14") (pinfunction "CBUS3_14") (pintype "bidirectional"))
    )
    (net (code "64") (name "unconnected-(IC2-CBUS4-Pad12)") (class "Default")
      (node (ref "IC2") (pin "12") (pinfunction "CBUS4_12") (pintype "bidirectional"))
    )
    (net (code "65") (name "unconnected-(IC2-OSCI-Pad27)") (class "Default")
      (node (ref "IC2") (pin "27") (pinfunction "OSCI_27") (pintype "input"))
    )
    (net (code "66") (name "unconnected-(IC2-OSCO-Pad28)") (class "Default")
      (node (ref "IC2") (pin "28") (pinfunction "OSCO_28") (pintype "output"))
    )
    (net (code "67") (name "unconnected-(IC2-~{CTS}-Pad11)") (class "Default")
      (node (ref "IC2") (pin "11") (pinfunction "~{CTS}_11") (pintype "input"))
    )
    (net (code "68") (name "unconnected-(IC2-~{DCD}-Pad10)") (class "Default")
      (node (ref "IC2") (pin "10") (pinfunction "~{DCD}_10") (pintype "input"))
    )
    (net (code "69") (name "unconnected-(IC2-~{DSR}-Pad9)") (class "Default")
      (node (ref "IC2") (pin "9") (pinfunction "~{DSR}_9") (pintype "input"))
    )
    (net (code "70") (name "unconnected-(IC2-~{DTR}-Pad2)") (class "Default")
      (node (ref "IC2") (pin "2") (pinfunction "~{DTR}_2") (pintype "output"))
    )
    (net (code "71") (name "unconnected-(IC2-~{RI}-Pad6)") (class "Default")
      (node (ref "IC2") (pin "6") (pinfunction "~{RI}_6") (pintype "input"))
    )
    (net (code "72") (name "unconnected-(IC2-~{RTS}-Pad3)") (class "Default")
      (node (ref "IC2") (pin "3") (pinfunction "~{RTS}_3") (pintype "output"))
    )
    (net (code "73") (name "unconnected-(IC4-PA3-Pad1)") (class "Default")
      (node (ref "IC4") (pin "1") (pinfunction "PA3_1") (pintype "bidirectional"))
    )
    (net (code "74") (name "unconnected-(IC4-PA4-Pad2)") (class "Default")
      (node (ref "IC4") (pin "2") (pinfunction "PA4_2") (pintype "bidirectional"))
    )
    (net (code "75") (name "unconnected-(IC4-PB1-Pad7)") (class "Default")
      (node (ref "IC4") (pin "7") (pinfunction "PB1_7") (pintype "bidirectional"))
    )
    (net (code "76") (name "unconnected-(IC4-PB2-Pad8)") (class "Default")
      (node (ref "IC4") (pin "8") (pinfunction "PB2_8") (pintype "bidirectional"))
    )
    (net (code "77") (name "unconnected-(IC4-PC0-Pad16)") (class "Default")
      (node (ref "IC4") (pin "16") (pinfunction "PC0_16") (pintype "bidirectional"))
    )
    (net (code "78") (name "unconnected-(IC4-PC1-Pad17)") (class "Default")
      (node (ref "IC4") (pin "17") (pinfunction "PC1_17") (pintype "bidirectional"))
    )
    (net (code "79") (name "unconnected-(IC4-PD3-Pad29)") (class "Default")
      (node (ref "IC4") (pin "29") (pinfunction "PD3_29") (pintype "bidirectional"))
    )
    (net (code "80") (name "unconnected-(IC4-PD4-Pad30)") (class "Default")
      (node (ref "IC4") (pin "30") (pinfunction "PD4_30") (pintype "bidirectional"))
    )
    (net (code "81") (name "unconnected-(IC4-PE3-Pad39)") (class "Default")
      (node (ref "IC4") (pin "39") (pinfunction "PE3_39") (pintype "bidirectional"))
    )
    (net (code "82") (name "unconnected-(IC4-PE4-Pad40)") (class "Default")
      (node (ref "IC4") (pin "40") (pinfunction "PE4_40") (pintype "bidirectional"))
    )
    (net (code "83") (name "unconnected-(IC4-PF3-Pad49)") (class "Default")
      (node (ref "IC4") (pin "49") (pinfunction "PF3_49") (pintype "bidirectional"))
    )
    (net (code "84") (name "unconnected-(IC4-PF4-Pad50)") (class "Default")
      (node (ref "IC4") (pin "50") (pinfunction "PF4_50") (pintype "bidirectional"))
    )
    (net (code "85") (name "unconnected-(SV1-Pad7)") (class "Default")
      (node (ref "SV1") (pin "7") (pinfunction "7_7") (pintype "passive"))
    )
    (net (code "86") (name "unconnected-(SV1-Pad8)") (class "Default")
      (node (ref "SV1") (pin "8") (pinfunction "8_8") (pintype "passive"))
    )
  )
)
